# Sheet1.net
KiCad netlist of a schematic drawn in Altium Designer
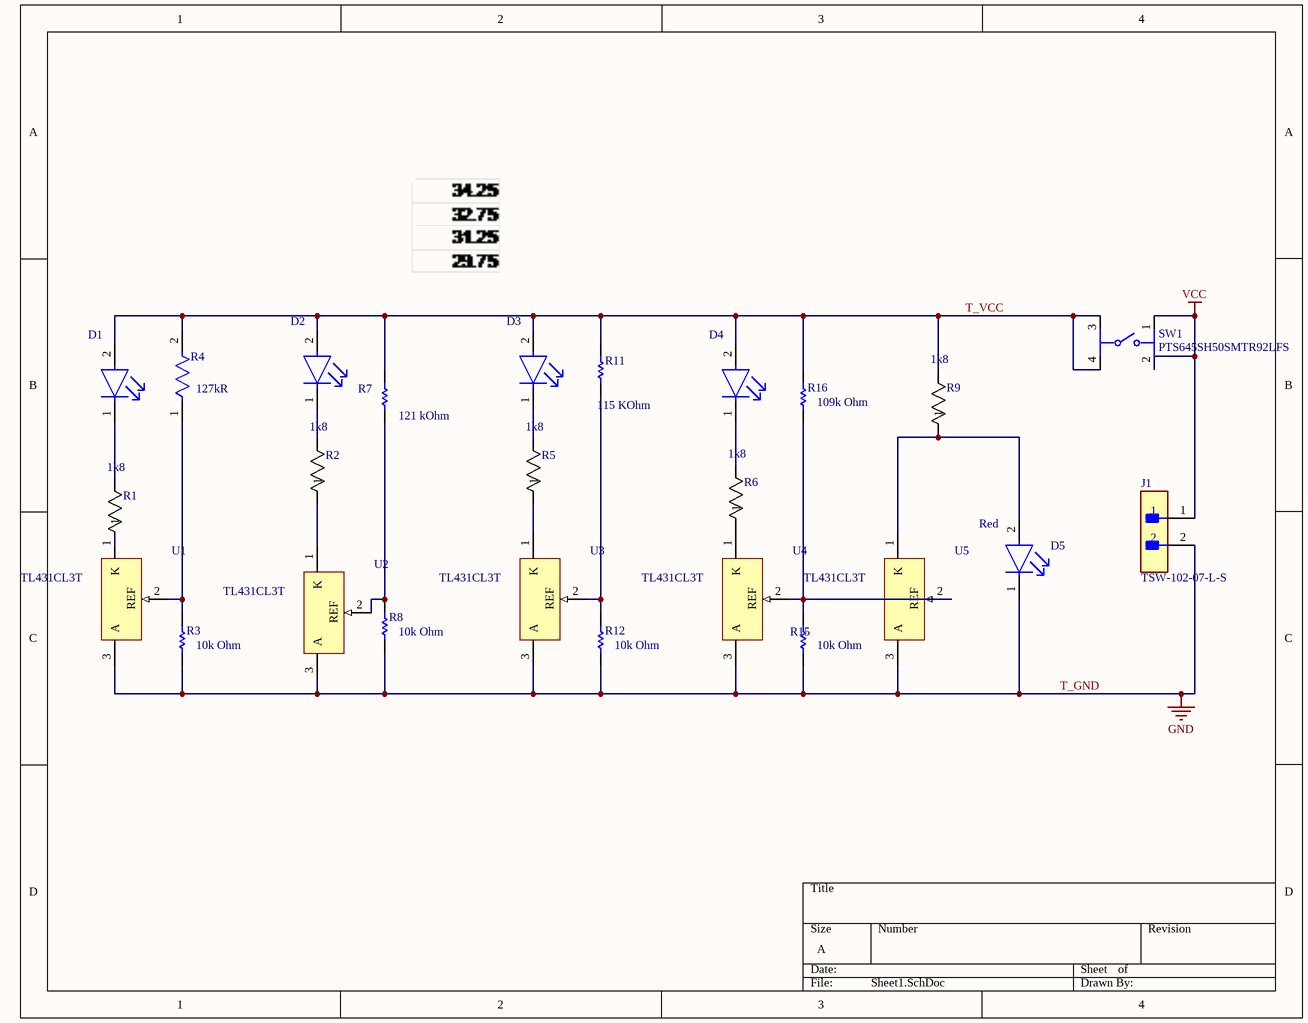
[diagram p0: Sheet1.SchDoc]

(export (version "E")
  (design (tool "Eeschema 10.0.6"))
  (components
    (comp (ref "D1")
      (value "LTST-C193KGKT-5A")
      (footprint "FP-LTST-C193KGKT-5A-MFG")
      (description "LED GREEN CLEAR CHIP SMD")
      (libsource (lib "Altium Content Vault") (part "8706943c75ba83719d021d2fdc84c58"))
    )
    (comp (ref "D2")
      (value "LTST-C193KGKT-5A")
      (footprint "FP-LTST-C193KGKT-5A-MFG")
      (description "LED GREEN CLEAR CHIP SMD")
      (libsource (lib "Altium Content Vault") (part "8706943c75ba83719d021d2fdc84c58"))
    )
    (comp (ref "D3")
      (value "LTST-C193KGKT-5A")
      (footprint "FP-LTST-C193KGKT-5A-MFG")
      (description "LED GREEN CLEAR CHIP SMD")
      (libsource (lib "Altium Content Vault") (part "8706943c75ba83719d021d2fdc84c58"))
    )
    (comp (ref "D4")
      (value "LTST-C193KGKT-5A")
      (footprint "FP-LTST-C193KGKT-5A-MFG")
      (description "LED GREEN CLEAR CHIP SMD")
      (libsource (lib "Altium Content Vault") (part "8706943c75ba83719d021d2fdc84c58"))
    )
    (comp (ref "D5")
      (value "LTST-C193KRKT-5A")
      (footprint "FP-LTST-C193KRKT-5A-MFG")
      (description "LED RED CLEAR CHIP SMD")
      (fields (field (name "ILLUMINATION COLOR") "Red"))
      (libsource (lib "Altium Content Vault") (part "8706943c75ba83719d021d2fdc84c58"))
    )
    (comp (ref "J1")
      (value "TSW-102-07-L-S")
      (footprint "FP-TSW-102-07-L-S-MFG")
      (description "CONN HEADER VERT 2POS 2.54MM")
      (libsource (lib "Altium Content Vault") (part "3bc925449376181038e59eaffc5286c"))
    )
    (comp (ref "R1")
      (value "RMCF2512JT1K80")
      (footprint "RES_RMCF2512_STP")
      (description "No Description Available")
      (fields (field (name "RESISTANCE") "1k8"))
      (libsource (lib "RMCF2512JT1K80") (part "RMCF2512JT1K80"))
    )
    (comp (ref "R2")
      (value "RMCF2512JT1K80")
      (footprint "RES_RMCF2512_STP")
      (description "No Description Available")
      (fields (field (name "RESISTANCE") "1k8"))
      (libsource (lib "RMCF2512JT1K80") (part "RMCF2512JT1K80"))
    )
    (comp (ref "R3")
      (value "10k Ohm")
      (footprint "RESC1609X50X30NL8T20")
      (description "Chip Resistor, 10 KOhm, +/- 1%, 100 mW, -55 to 155 degC, 0603 (1608 Metric), RoHS, Tape and Reel")
      (fields
        (field (name "MANUFACTURER") "Vishay Semiconductor")
        (field (name "Comment") "CRCW060310K0FKEA")
      )
      (libsource (lib "Altium Content Vault") (part "RES-2"))
    )
    (comp (ref "R4")
      (value "CRCW0603127KFKEA")
      (footprint "FP-CRCW0603-e3-IPC_A")
      (description "RES Thick Film, 127kΩ, 1%, 0.1W, 100ppm/°C, 0603")
      (fields (field (name "TOLERANCE") "1%") (field (name "RESISTANCE") "127kR"))
      (libsource (lib "Altium Content Vault") (part "1029c3af85768c4190bb7ad29bc67b5"))
    )
    (comp (ref "R5")
      (value "RMCF2512JT1K80")
      (footprint "RES_RMCF2512_STP")
      (description "No Description Available")
      (fields (field (name "RESISTANCE") "1k8"))
      (libsource (lib "RMCF2512JT1K80") (part "RMCF2512JT1K80"))
    )
    (comp (ref "R6")
      (value "RMCF2512JT1K80")
      (footprint "RES_RMCF2512_STP")
      (description "No Description Available")
      (fields (field (name "RESISTANCE") "1k8"))
      (libsource (lib "RMCF2512JT1K80") (part "RMCF2512JT1K80"))
    )
    (comp (ref "R7")
      (value "121 kOhm")
      (footprint "RESC1608X55X25ML10T15")
      (fields (field (name "MANUFACTURER") "Yageo") (field (name "PART NUMBER") "RC0603FR-07121KL"))
      (libsource (lib "Altium Content Vault") (part "RES"))
    )
    (comp (ref "R8")
      (value "10k Ohm")
      (footprint "RESC1609X50X30NL8T20")
      (description "Chip Resistor, 10 KOhm, +/- 1%, 100 mW, -55 to 155 degC, 0603 (1608 Metric), RoHS, Tape and Reel")
      (fields
        (field (name "MANUFACTURER") "Vishay Semiconductor")
        (field (name "Comment") "CRCW060310K0FKEA")
      )
      (libsource (lib "Altium Content Vault") (part "RES-2"))
    )
    (comp (ref "R9")
      (value "RMCF2512JT1K80")
      (footprint "RES_RMCF2512_STP")
      (description "No Description Available")
      (fields (field (name "RESISTANCE") "1k8"))
      (libsource (lib "RMCF2512JT1K80") (part "RMCF2512JT1K80"))
    )
    (comp (ref "R11")
      (value "115 KOhm")
      (footprint "RESC1608X55X30ML15T15")
      (fields (field (name "MANUFACTURER") "Panasonic") (field (name "PART NUMBER") "ERJ-3EKF1153V"))
      (libsource (lib "Altium Content Vault") (part "RES"))
    )
    (comp (ref "R12")
      (value "10k Ohm")
      (footprint "RESC1609X50X30NL8T20")
      (description "Chip Resistor, 10 KOhm, +/- 1%, 100 mW, -55 to 155 degC, 0603 (1608 Metric), RoHS, Tape and Reel")
      (fields
        (field (name "MANUFACTURER") "Vishay Semiconductor")
        (field (name "Comment") "CRCW060310K0FKEA")
      )
      (libsource (lib "Altium Content Vault") (part "RES-2"))
    )
    (comp (ref "R15")
      (value "10k Ohm")
      (footprint "RESC1609X50X30NL8T20")
      (description "Chip Resistor, 10 KOhm, +/- 1%, 100 mW, -55 to 155 degC, 0603 (1608 Metric), RoHS, Tape and Reel")
      (fields
        (field (name "MANUFACTURER") "Vishay Semiconductor")
        (field (name "Comment") "CRCW060310K0FKEA")
      )
      (libsource (lib "Altium Content Vault") (part "RES-2"))
    )
    (comp (ref "R16")
      (value "109k Ohm")
      (footprint "RESC2013X60X35NL10T20")
      (fields (field (name "PART NUMBER") "RC0805FR-109K09L") (field (name "MANUFACTURER") "Yageo"))
      (libsource (lib "Altium Content Vault") (part "RES"))
    )
    (comp (ref "SW1")
      (value "PTS645SH50SMTR92LFS")
      (footprint "FP-PTS645SH50SMTR92LFS-MFG")
      (description "SWITCH TACTILE SPST-NO 0.05A 12V")
      (libsource (lib "Altium Content Vault") (part "1adf0dd01260c80cf25a44bfd6b99ba"))
    )
    (comp (ref "U1")
      (value "TL431CL3T")
      (footprint "SOT23-3_M")
      (description "Programmable Voltage Reference, 2.5 to 36V, 3-Pin SOT23-3, Tape and Reel")
      (libsource (lib "Altium Content Vault") (part "PM-REF-431-IL3"))
    )
    (comp (ref "U2")
      (value "TL431CL3T")
      (footprint "SOT23-3_M")
      (description "Programmable Voltage Reference, 2.5 to 36V, 3-Pin SOT23-3, Tape and Reel")
      (libsource (lib "Altium Content Vault") (part "PM-REF-431-IL3"))
    )
    (comp (ref "U3")
      (value "TL431CL3T")
      (footprint "SOT23-3_M")
      (description "Programmable Voltage Reference, 2.5 to 36V, 3-Pin SOT23-3, Tape and Reel")
      (libsource (lib "Altium Content Vault") (part "PM-REF-431-IL3"))
    )
    (comp (ref "U4")
      (value "TL431CL3T")
      (footprint "SOT23-3_M")
      (description "Programmable Voltage Reference, 2.5 to 36V, 3-Pin SOT23-3, Tape and Reel")
      (libsource (lib "Altium Content Vault") (part "PM-REF-431-IL3"))
    )
    (comp (ref "U5")
      (value "TL431CL3T")
      (footprint "SOT23-3_M")
      (description "Programmable Voltage Reference, 2.5 to 36V, 3-Pin SOT23-3, Tape and Reel")
      (libsource (lib "Altium Content Vault") (part "PM-REF-431-IL3"))
    )
  )
  (nets
    (net (code "1") (name "/T_VCC") (class "Default")
      (node (ref "D1") (pin "2") (pinfunction "A_2") (pintype "passive"))
      (node (ref "D2") (pin "2") (pinfunction "A_2") (pintype "passive"))
      (node (ref "D3") (pin "2") (pinfunction "A_2") (pintype "passive"))
      (node (ref "D4") (pin "2") (pinfunction "A_2") (pintype "passive"))
      (node (ref "R11") (pin "2") (pinfunction "2_2") (pintype "passive"))
      (node (ref "R16") (pin "2") (pinfunction "2_2") (pintype "passive"))
      (node (ref "R4") (pin "2") (pinfunction "2_2") (pintype "passive"))
      (node (ref "R7") (pin "2") (pinfunction "2_2") (pintype "passive"))
      (node (ref "R9") (pin "2") (pinfunction "2_2") (pintype "passive"))
      (node (ref "SW1") (pin "3") (pinfunction "3_3") (pintype "passive"))
      (node (ref "SW1") (pin "4") (pinfunction "4_4") (pintype "passive"))
    )
    (net (code "2") (name "GND") (class "Default")
      (node (ref "D5") (pin "1") (pinfunction "C_1") (pintype "passive"))
      (node (ref "J1") (pin "2") (pinfunction "2_2") (pintype "passive"))
      (node (ref "R12") (pin "1") (pinfunction "1_1") (pintype "passive"))
      (node (ref "R15") (pin "1") (pinfunction "1_1") (pintype "passive"))
      (node (ref "R3") (pin "1") (pinfunction "1_1") (pintype "passive"))
      (node (ref "R8") (pin "1") (pinfunction "1_1") (pintype "passive"))
      (node (ref "U1") (pin "3") (pinfunction "A_3") (pintype "passive"))
      (node (ref "U2") (pin "3") (pinfunction "A_3") (pintype "passive"))
      (node (ref "U3") (pin "3") (pinfunction "A_3") (pintype "passive"))
      (node (ref "U4") (pin "3") (pinfunction "A_3") (pintype "passive"))
      (node (ref "U5") (pin "3") (pinfunction "A_3") (pintype "passive"))
    )
    (net (code "3") (name "Net-(D1-C)") (class "Default")
      (node (ref "D1") (pin "1") (pinfunction "C_1") (pintype "passive"))
      (node (ref "R1") (pin "2") (pinfunction "2_2") (pintype "passive"))
    )
    (net (code "4") (name "Net-(D2-C)") (class "Default")
      (node (ref "D2") (pin "1") (pinfunction "C_1") (pintype "passive"))
      (node (ref "R2") (pin "2") (pinfunction "2_2") (pintype "passive"))
    )
    (net (code "5") (name "Net-(D3-C)") (class "Default")
      (node (ref "D3") (pin "1") (pinfunction "C_1") (pintype "passive"))
      (node (ref "R5") (pin "2") (pinfunction "2_2") (pintype "passive"))
    )
    (net (code "6") (name "Net-(D4-C)") (class "Default")
      (node (ref "D4") (pin "1") (pinfunction "C_1") (pintype "passive"))
      (node (ref "R6") (pin "2") (pinfunction "2_2") (pintype "passive"))
    )
    (net (code "7") (name "Net-(D5-A)") (class "Default")
      (node (ref "D5") (pin "2") (pinfunction "A_2") (pintype "passive"))
      (node (ref "R9") (pin "1") (pinfunction "1_1") (pintype "passive"))
      (node (ref "U5") (pin "1") (pinfunction "K_1") (pintype "passive"))
    )
    (net (code "8") (name "Net-(U1-K)") (class "Default")
      (node (ref "R1") (pin "1") (pinfunction "1_1") (pintype "passive"))
      (node (ref "U1") (pin "1") (pinfunction "K_1") (pintype "passive"))
    )
    (net (code "9") (name "Net-(U1-REF)") (class "Default")
      (node (ref "R3") (pin "2") (pinfunction "2_2") (pintype "passive"))
      (node (ref "R4") (pin "1") (pinfunction "1_1") (pintype "passive"))
      (node (ref "U1") (pin "2") (pinfunction "REF_2") (pintype "input"))
    )
    (net (code "10") (name "Net-(U2-K)") (class "Default")
      (node (ref "R2") (pin "1") (pinfunction "1_1") (pintype "passive"))
      (node (ref "U2") (pin "1") (pinfunction "K_1") (pintype "passive"))
    )
    (net (code "11") (name "Net-(U2-REF)") (class "Default")
      (node (ref "R7") (pin "1") (pinfunction "1_1") (pintype "passive"))
      (node (ref "R8") (pin "2") (pinfunction "2_2") (pintype "passive"))
      (node (ref "U2") (pin "2") (pinfunction "REF_2") (pintype "input"))
    )
    (net (code "12") (name "Net-(U3-K)") (class "Default")
      (node (ref "R5") (pin "1") (pinfunction "1_1") (pintype "passive"))
      (node (ref "U3") (pin "1") (pinfunction "K_1") (pintype "passive"))
    )
    (net (code "13") (name "Net-(U3-REF)") (class "Default")
      (node (ref "R11") (pin "1") (pinfunction "1_1") (pintype "passive"))
      (node (ref "R12") (pin "2") (pinfunction "2_2") (pintype "passive"))
      (node (ref "U3") (pin "2") (pinfunction "REF_2") (pintype "input"))
    )
    (net (code "14") (name "Net-(U4-K)") (class "Default")
      (node (ref "R6") (pin "1") (pinfunction "1_1") (pintype "passive"))
      (node (ref "U4") (pin "1") (pinfunction "K_1") (pintype "passive"))
    )
    (net (code "15") (name "Net-(U4-REF)") (class "Default")
      (node (ref "R15") (pin "2") (pinfunction "2_2") (pintype "passive"))
      (node (ref "R16") (pin "1") (pinfunction "1_1") (pintype "passive"))
      (node (ref "U4") (pin "2") (pinfunction "REF_2") (pintype "input"))
      (node (ref "U5") (pin "2") (pinfunction "REF_2") (pintype "input"))
    )
    (net (code "16") (name "VCC") (class "Default")
      (node (ref "J1") (pin "1") (pinfunction "1_1") (pintype "passive"))
      (node (ref "SW1") (pin "1") (pinfunction "1_1") (pintype "passive"))
      (node (ref "SW1") (pin "2") (pinfunction "2_2") (pintype "passive"))
    )
  )
)
